# Dot_Matrix.net
KiCad netlist of a schematic drawn in Altium Designer
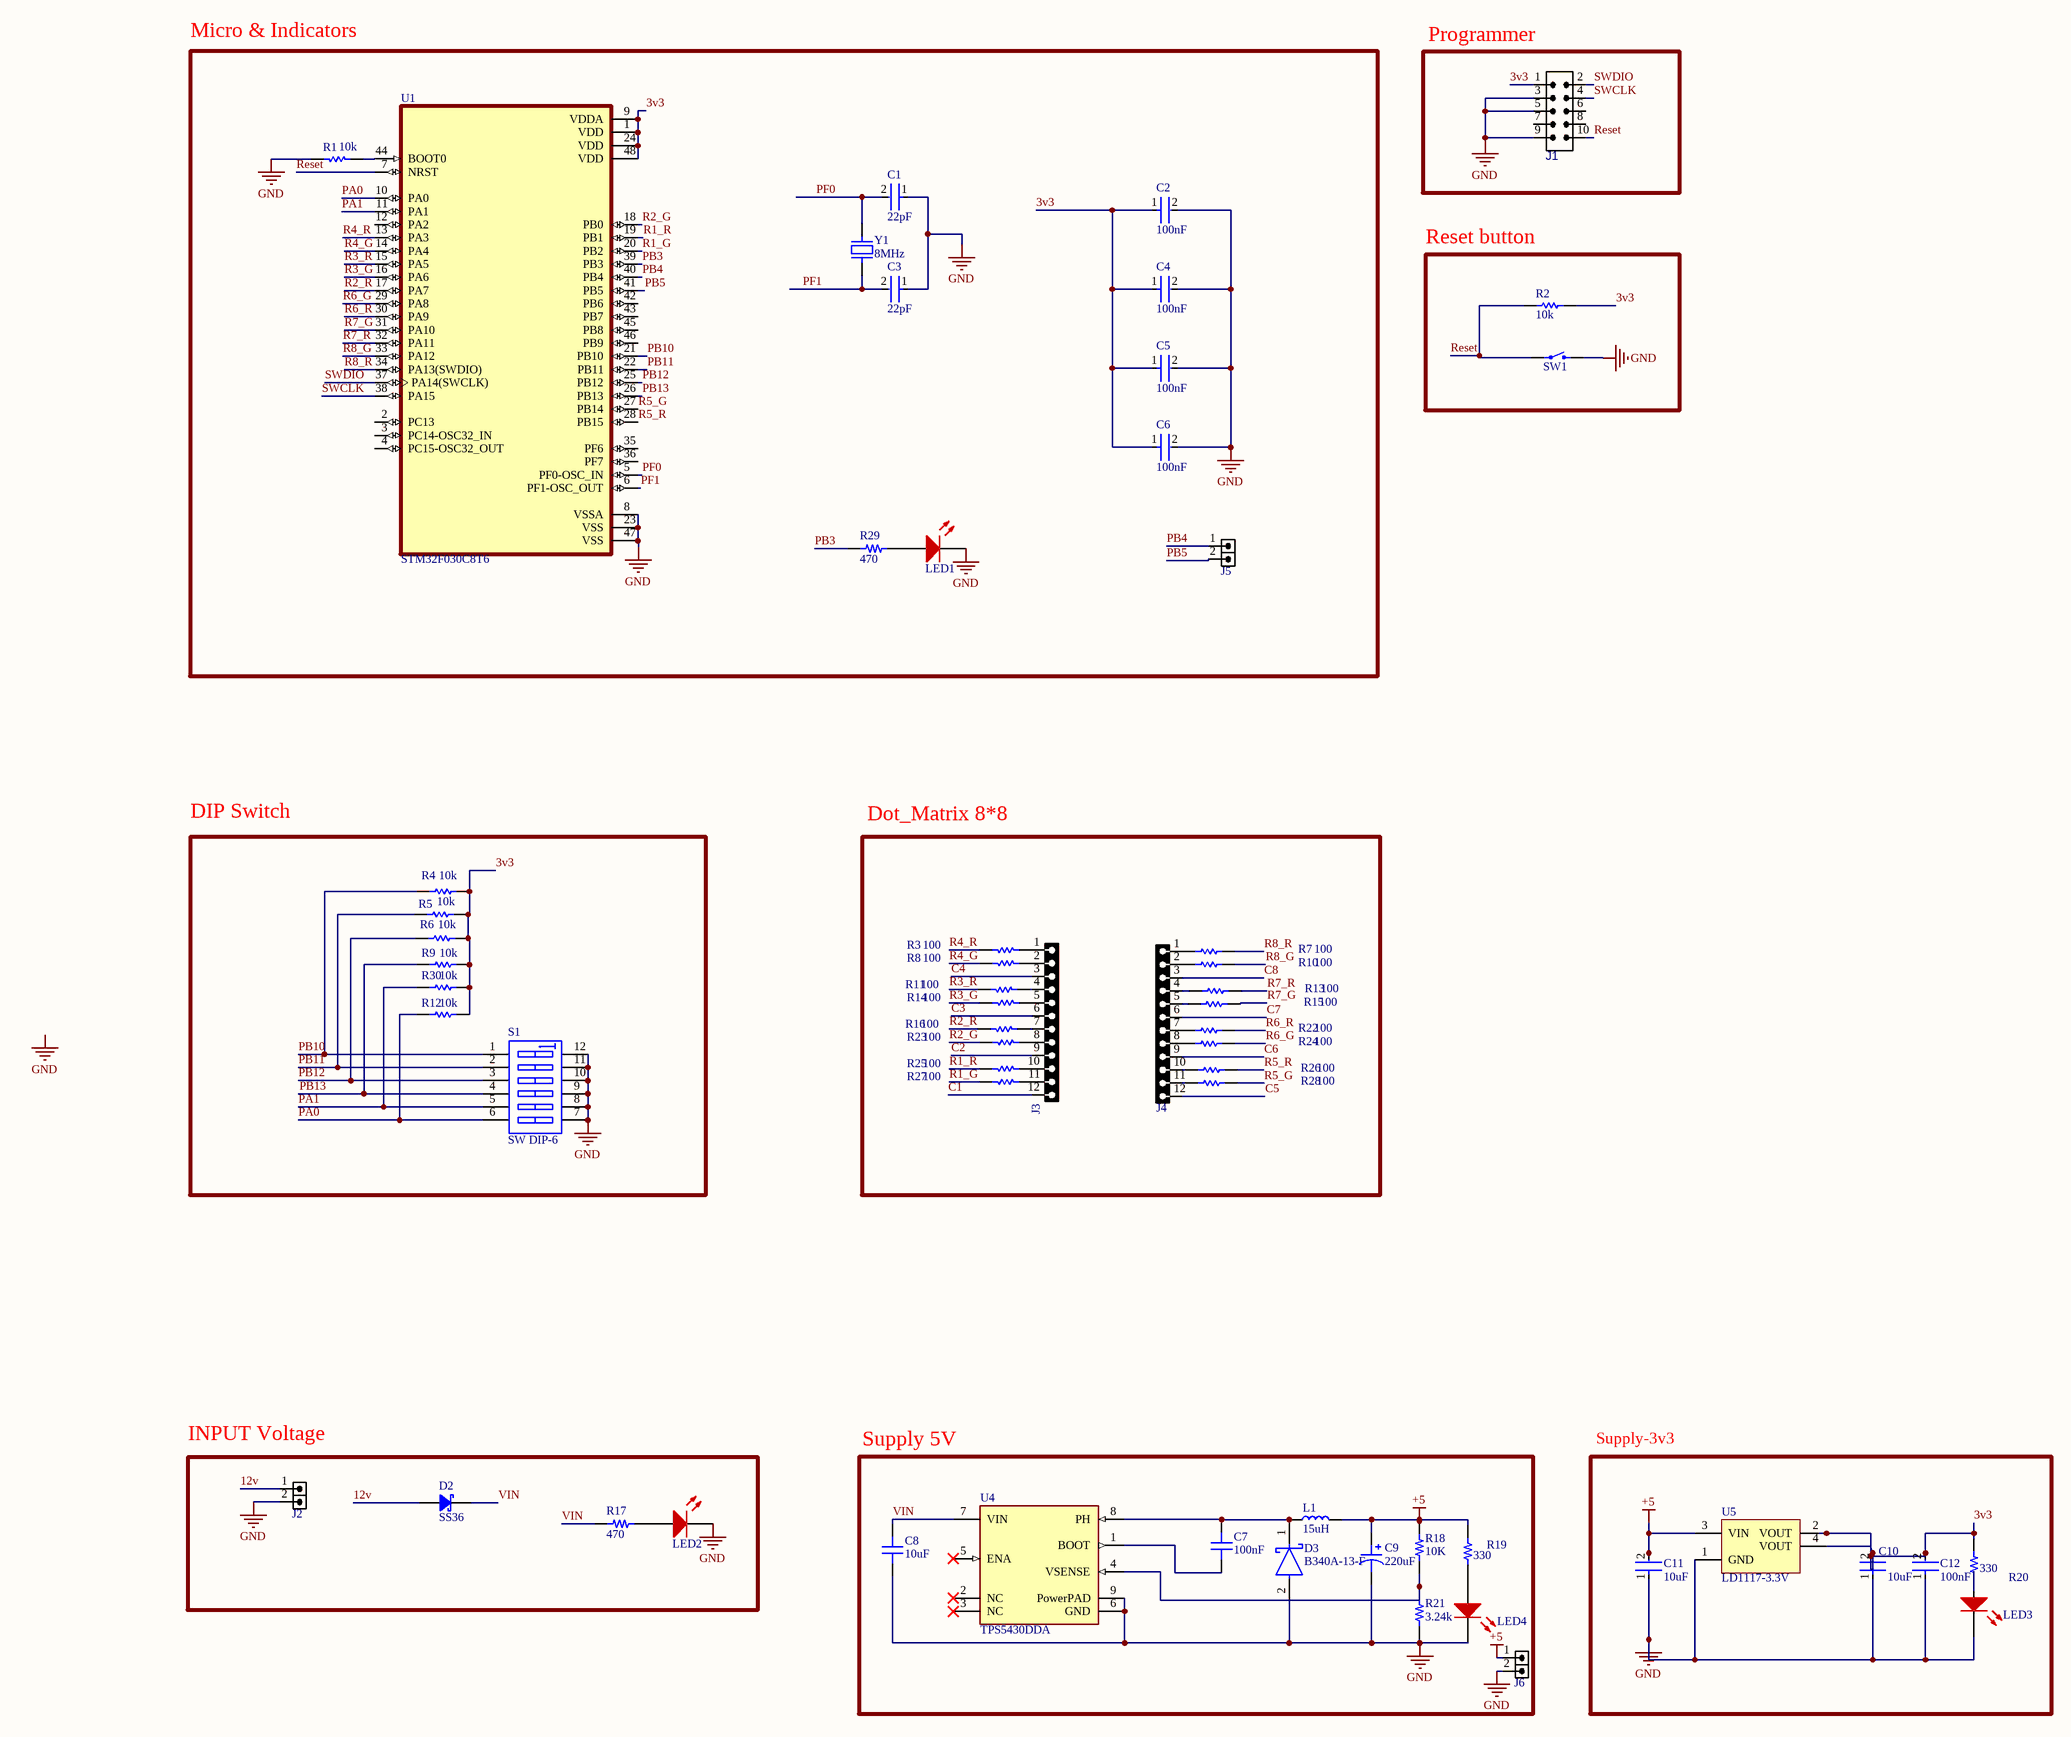
[diagram p0: Dot_Matrix.SchDoc]

(export (version "E")
  (design (tool "Eeschema 10.0.6"))
  (components
    (comp (ref "C1")
      (value "22pF")
      (footprint "FP-C0805C-DN-MFG")
      (description "CAP CER 0.22UF 50V X7R 0805")
      (fields
        (field (name "MANUFACTURER") "KEMET")
        (field (name "OCTOPART") "https://octopart.com/c0805c224k5ractu-kemet-144670")
      )
      (libsource (lib "Altium Content Vault") (part "b4654b650e69147ec39a6b967a45e02"))
    )
    (comp (ref "C2")
      (value "100nF")
      (footprint "FP-C0805C-DN-MFG")
      (description "CAP CER 0.22UF 50V X7R 0805")
      (fields
        (field (name "MANUFACTURER") "KEMET")
        (field (name "OCTOPART") "https://octopart.com/c0805c224k5ractu-kemet-144670")
      )
      (libsource (lib "Altium Content Vault") (part "b4654b650e69147ec39a6b967a45e02"))
    )
    (comp (ref "C3")
      (value "22pF")
      (footprint "FP-C0805C-DN-MFG")
      (description "CAP CER 0.22UF 50V X7R 0805")
      (fields
        (field (name "MANUFACTURER") "KEMET")
        (field (name "OCTOPART") "https://octopart.com/c0805c224k5ractu-kemet-144670")
      )
      (libsource (lib "Altium Content Vault") (part "b4654b650e69147ec39a6b967a45e02"))
    )
    (comp (ref "C4")
      (value "100nF")
      (footprint "FP-C0805C-DN-MFG")
      (description "CAP CER 0.22UF 50V X7R 0805")
      (fields
        (field (name "MANUFACTURER") "KEMET")
        (field (name "OCTOPART") "https://octopart.com/c0805c224k5ractu-kemet-144670")
      )
      (libsource (lib "Altium Content Vault") (part "b4654b650e69147ec39a6b967a45e02"))
    )
    (comp (ref "C5")
      (value "100nF")
      (footprint "FP-C0805C-DN-MFG")
      (description "CAP CER 0.22UF 50V X7R 0805")
      (fields
        (field (name "MANUFACTURER") "KEMET")
        (field (name "OCTOPART") "https://octopart.com/c0805c224k5ractu-kemet-144670")
      )
      (libsource (lib "Altium Content Vault") (part "b4654b650e69147ec39a6b967a45e02"))
    )
    (comp (ref "C6")
      (value "100nF")
      (footprint "FP-C0805C-DN-MFG")
      (description "CAP CER 0.22UF 50V X7R 0805")
      (fields
        (field (name "MANUFACTURER") "KEMET")
        (field (name "OCTOPART") "https://octopart.com/c0805c224k5ractu-kemet-144670")
      )
      (libsource (lib "Altium Content Vault") (part "b4654b650e69147ec39a6b967a45e02"))
    )
    (comp (ref "C7")
      (value "100nF")
      (footprint "CAP 0805_2012")
      (description "SMT Capacitor")
      (libsource (lib "Capacitor") (part "Cap 0805"))
    )
    (comp (ref "C8")
      (value "10uF")
      (footprint "CAP 0805_2012")
      (description "SMT Capacitor")
      (libsource (lib "Capacitor") (part "Cap 0805"))
    )
    (comp (ref "C9")
      (value "220uF")
      (footprint "CAP TANSMD 1206_3216 CASE A")
      (description "SMT Tantalum Capacitor")
      (libsource (lib "Capacitor") (part "Cap Tan Case A"))
    )
    (comp (ref "C10")
      (value "10uF")
      (footprint "FP-C0805C-DN-MFG")
      (description "CAP CER 0.22UF 50V X7R 0805")
      (fields
        (field (name "MANUFACTURER") "KEMET")
        (field (name "OCTOPART") "https://octopart.com/c0805c224k5ractu-kemet-144670")
      )
      (libsource (lib "Altium Content Vault") (part "b4654b650e69147ec39a6b967a45e02"))
    )
    (comp (ref "C11")
      (value "10uF")
      (footprint "FP-C0805C-DN-MFG")
      (description "CAP CER 0.22UF 50V X7R 0805")
      (fields
        (field (name "MANUFACTURER") "KEMET")
        (field (name "OCTOPART") "https://octopart.com/c0805c224k5ractu-kemet-144670")
      )
      (libsource (lib "Altium Content Vault") (part "b4654b650e69147ec39a6b967a45e02"))
    )
    (comp (ref "C12")
      (value "100nF")
      (footprint "FP-C0805C-DN-MFG")
      (description "CAP CER 0.22UF 50V X7R 0805")
      (fields
        (field (name "MANUFACTURER") "KEMET")
        (field (name "OCTOPART") "https://octopart.com/c0805c224k5ractu-kemet-144670")
      )
      (libsource (lib "Altium Content Vault") (part "b4654b650e69147ec39a6b967a45e02"))
    )
    (comp (ref "D2")
      (value "SS36")
      (footprint "DO-214AA SMB")
      (description "Diode Schottky 60V 3A Surface Mount DO-214AB (SMC)")
      (fields (field (name "PARTNUMBER") "SS36-E3/57T"))
      (libsource (lib "Diode") (part "SS36 (SMD SMC)"))
    )
    (comp (ref "D3")
      (value "B340A-13-F")
      (footprint "FP-SMA-MFG")
      (description "DIODE SCHOTTKY 40V 3A SMA")
      (fields (field (name "VOLTAGE") "40V"))
      (libsource (lib "Altium Content Vault") (part "1d6ec82d83fb6aee721767c19dac4b9"))
    )
    (comp (ref "J1")
      (value "IDC_2X5")
      (footprint "IDC_2X5")
      (description "CONN, IDC, Male, pitch: 2.54mm, 10POS")
      (libsource (lib "Conn Header") (part "IDC_2X5"))
    )
    (comp (ref "J2")
      (value "HDRM2")
      (footprint "HDR_1X2")
      (description "CONN, HEADER, Male, pitch: 2.54mm, 2POS")
      (libsource (lib "Conn Header") (part "HDR_1X2"))
    )
    (comp (ref "J3")
      (value "HDRF12")
      (footprint "HDR_F_1X12")
      (description "CONN, HEADER, Female, pitch: 2.54mm, 12POS")
      (libsource (lib "Conn Header") (part "HDR_F_1X12"))
    )
    (comp (ref "J4")
      (value "HDRF12")
      (footprint "HDR_F_1X12")
      (description "CONN, HEADER, Female, pitch: 2.54mm, 12POS")
      (libsource (lib "") (part "HDR_F_1X12_1"))
    )
    (comp (ref "J5")
      (value "HDRM2")
      (footprint "HDR_1X2")
      (description "CONN, HEADER, Male, pitch: 2.54mm, 2POS")
      (libsource (lib "Conn Header") (part "HDR_1X2"))
    )
    (comp (ref "J6")
      (value "HDRM2")
      (footprint "HDR_1X2")
      (description "CONN, HEADER, Male, pitch: 2.54mm, 2POS")
      (libsource (lib "Conn Header") (part "HDR_1X2"))
    )
    (comp (ref "L1")
      (value "15uH")
      (footprint "IND 0805_2012")
      (description "SMT Inductor")
      (libsource (lib "Inductor") (part "Ind 0805"))
    )
    (comp (ref "LED1")
      (value "LED SMD 0805 RED")
      (footprint "LED_0805_RED")
      (libsource (lib "Led") (part "LED SMD 0805 RED"))
    )
    (comp (ref "LED2")
      (value "LED SMD 0805 RED")
      (footprint "LED_0805_RED")
      (libsource (lib "Led") (part "LED SMD 0805 RED"))
    )
    (comp (ref "LED3")
      (value "LED SMD 0805 RED")
      (footprint "LED_0805_RED")
      (libsource (lib "Led") (part "LED SMD 0805 RED"))
    )
    (comp (ref "LED4")
      (value "LED SMD 0805 RED")
      (footprint "LED_0805_RED")
      (libsource (lib "Led") (part "LED SMD 0805 RED"))
    )
    (comp (ref "R1")
      (value "10k")
      (footprint "RESC2013X60X35ML10T20")
      (fields (field (name "TOLERANCE") "5%") (field (name "MANUFACTURER") "Yageo"))
      (libsource (lib "Altium Content Vault") (part "RES-2"))
    )
    (comp (ref "R2")
      (value "10k")
      (footprint "RESC2013X60X35ML10T20")
      (fields (field (name "TOLERANCE") "5%") (field (name "MANUFACTURER") "Yageo"))
      (libsource (lib "Altium Content Vault") (part "RES-2"))
    )
    (comp (ref "R3")
      (value "100")
      (footprint "RESC2013X60X35ML10T20")
      (fields (field (name "TOLERANCE") "5%") (field (name "MANUFACTURER") "Yageo"))
      (libsource (lib "Altium Content Vault") (part "RES-2"))
    )
    (comp (ref "R4")
      (value "10k")
      (footprint "RESC2013X60X35ML10T20")
      (fields (field (name "TOLERANCE") "5%") (field (name "MANUFACTURER") "Yageo"))
      (libsource (lib "Altium Content Vault") (part "RES-2"))
    )
    (comp (ref "R5")
      (value "10k")
      (footprint "RESC2013X60X35ML10T20")
      (fields (field (name "TOLERANCE") "5%") (field (name "MANUFACTURER") "Yageo"))
      (libsource (lib "Altium Content Vault") (part "RES-2"))
    )
    (comp (ref "R6")
      (value "10k")
      (footprint "RESC2013X60X35ML10T20")
      (fields (field (name "TOLERANCE") "5%") (field (name "MANUFACTURER") "Yageo"))
      (libsource (lib "Altium Content Vault") (part "RES-2"))
    )
    (comp (ref "R7")
      (value "100")
      (footprint "RESC2013X60X35ML10T20")
      (fields (field (name "TOLERANCE") "5%") (field (name "MANUFACTURER") "Yageo"))
      (libsource (lib "Altium Content Vault") (part "RES-2"))
    )
    (comp (ref "R8")
      (value "100")
      (footprint "RESC2013X60X35ML10T20")
      (fields (field (name "TOLERANCE") "5%") (field (name "MANUFACTURER") "Yageo"))
      (libsource (lib "Altium Content Vault") (part "RES-2"))
    )
    (comp (ref "R9")
      (value "10k")
      (footprint "RESC2013X60X35ML10T20")
      (fields (field (name "TOLERANCE") "5%") (field (name "MANUFACTURER") "Yageo"))
      (libsource (lib "Altium Content Vault") (part "RES-2"))
    )
    (comp (ref "R10")
      (value "100")
      (footprint "RESC2013X60X35ML10T20")
      (fields (field (name "TOLERANCE") "5%") (field (name "MANUFACTURER") "Yageo"))
      (libsource (lib "Altium Content Vault") (part "RES-2"))
    )
    (comp (ref "R11")
      (value "100")
      (footprint "RESC2013X60X35ML10T20")
      (fields (field (name "TOLERANCE") "5%") (field (name "MANUFACTURER") "Yageo"))
      (libsource (lib "Altium Content Vault") (part "RES-2"))
    )
    (comp (ref "R12")
      (value "10k")
      (footprint "RESC2013X60X35ML10T20")
      (fields (field (name "TOLERANCE") "5%") (field (name "MANUFACTURER") "Yageo"))
      (libsource (lib "Altium Content Vault") (part "RES-2"))
    )
    (comp (ref "R13")
      (value "100")
      (footprint "RESC2013X60X35ML10T20")
      (fields (field (name "TOLERANCE") "5%") (field (name "MANUFACTURER") "Yageo"))
      (libsource (lib "Altium Content Vault") (part "RES-2"))
    )
    (comp (ref "R14")
      (value "100")
      (footprint "RESC2013X60X35ML10T20")
      (fields (field (name "TOLERANCE") "5%") (field (name "MANUFACTURER") "Yageo"))
      (libsource (lib "Altium Content Vault") (part "RES-2"))
    )
    (comp (ref "R15")
      (value "100")
      (footprint "RESC2013X60X35ML10T20")
      (fields (field (name "TOLERANCE") "5%") (field (name "MANUFACTURER") "Yageo"))
      (libsource (lib "Altium Content Vault") (part "RES-2"))
    )
    (comp (ref "R16")
      (value "100")
      (footprint "RESC2013X60X35ML10T20")
      (fields (field (name "TOLERANCE") "5%") (field (name "MANUFACTURER") "Yageo"))
      (libsource (lib "Altium Content Vault") (part "RES-2"))
    )
    (comp (ref "R17")
      (value "470")
      (footprint "RES 0805_2012")
      (description "SMT Resistor")
      (libsource (lib "Resistor") (part "Res 0805"))
    )
    (comp (ref "R18")
      (value "10K")
      (footprint "RES 0805_2012")
      (description "SMT Resistor")
      (libsource (lib "Resistor") (part "Res 0805"))
    )
    (comp (ref "R19")
      (value "330")
      (footprint "RES 0805_2012")
      (description "SMT Resistor")
      (libsource (lib "Resistor") (part "Res 0805"))
    )
    (comp (ref "R20")
      (value "330")
      (footprint "RES 0805_2012")
      (description "SMT Resistor")
      (libsource (lib "Resistor") (part "Res 0805"))
    )
    (comp (ref "R21")
      (value "3.24k")
      (footprint "RES 0805_2012")
      (description "SMT Resistor")
      (libsource (lib "Resistor") (part "Res 0805"))
    )
    (comp (ref "R22")
      (value "100")
      (footprint "RESC2013X60X35ML10T20")
      (fields (field (name "TOLERANCE") "5%") (field (name "MANUFACTURER") "Yageo"))
      (libsource (lib "Altium Content Vault") (part "RES-2"))
    )
    (comp (ref "R23")
      (value "100")
      (footprint "RESC2013X60X35ML10T20")
      (fields (field (name "TOLERANCE") "5%") (field (name "MANUFACTURER") "Yageo"))
      (libsource (lib "Altium Content Vault") (part "RES-2"))
    )
    (comp (ref "R24")
      (value "100")
      (footprint "RESC2013X60X35ML10T20")
      (fields (field (name "TOLERANCE") "5%") (field (name "MANUFACTURER") "Yageo"))
      (libsource (lib "Altium Content Vault") (part "RES-2"))
    )
    (comp (ref "R25")
      (value "100")
      (footprint "RESC2013X60X35ML10T20")
      (fields (field (name "TOLERANCE") "5%") (field (name "MANUFACTURER") "Yageo"))
      (libsource (lib "Altium Content Vault") (part "RES-2"))
    )
    (comp (ref "R26")
      (value "100")
      (footprint "RESC2013X60X35ML10T20")
      (fields (field (name "TOLERANCE") "5%") (field (name "MANUFACTURER") "Yageo"))
      (libsource (lib "Altium Content Vault") (part "RES-2"))
    )
    (comp (ref "R27")
      (value "100")
      (footprint "RESC2013X60X35ML10T20")
      (fields (field (name "TOLERANCE") "5%") (field (name "MANUFACTURER") "Yageo"))
      (libsource (lib "Altium Content Vault") (part "RES-2"))
    )
    (comp (ref "R28")
      (value "100")
      (footprint "RESC2013X60X35ML10T20")
      (fields (field (name "TOLERANCE") "5%") (field (name "MANUFACTURER") "Yageo"))
      (libsource (lib "Altium Content Vault") (part "RES-2"))
    )
    (comp (ref "R29")
      (value "470")
      (footprint "RES 0805_2012")
      (description "SMT Resistor")
      (libsource (lib "Resistor") (part "Res 0805"))
    )
    (comp (ref "R30")
      (value "10k")
      (footprint "RESC2013X60X35ML10T20")
      (fields (field (name "TOLERANCE") "5%") (field (name "MANUFACTURER") "Yageo"))
      (libsource (lib "Altium Content Vault") (part "RES-2"))
    )
    (comp (ref "S1")
      (value "SW DIP-6")
      (footprint "DIP-12/SW")
      (description "DIP Switch, 6 Position, SPST")
      (fields (field (name "PUBLISHER") "Altium Limited"))
      (libsource (lib "Miscellaneous Devices") (part "SW DIP-6"))
    )
    (comp (ref "SW1")
      (value "Tactile 2PIN 6X3.5mm H4.57mm (SMD)")
      (footprint "SWPBS_SPST_6X3X5")
      (description "Tactile Switch SPST-NO Top Actuated Surface Mount")
      (fields (field (name "PARTNUMBER") "FSMSMTR-ND"))
      (libsource (lib "Switch") (part "Tactile 2PIN 6X3.5mm H4.57mm (SMD)"))
    )
    (comp (ref "U1")
      (value "STM32F030C8T6")
      (footprint "QFP50P900X900X160-48N")
      (description "STM32F Series 32-bit 64 kB Flash 8 kB RAM ARM Based Microcontroller - LQFP-48")
      (libsource (lib "STM32F030C8T6") (part "STM32F030C8T6"))
    )
    (comp (ref "U4")
      (value "TPS5430DDA")
      (footprint "FP-DDA0008J-MFG")
      (description "IC REG BUCK ADJUSTABLE 3A 8SOPWR")
      (fields
        (field (name "MANUFACTURER") "Texas Instruments")
        (field (name "OCTOPART") "https://octopart.com/tps5430dda-texas+instruments-589977")
      )
      (libsource (lib "Altium Content Vault") (part "98da629940cea6febc5630bb55159f3"))
    )
    (comp (ref "U5")
      (value "LD1117-3.3V")
      (footprint "SOT-223-4 6.5X7MM P2.3MM")
      (description "Linear Voltage Regulator IC  1 Output  800mA SOT-223")
      (fields (field (name "PARTNUMBER") "LD1117S33CTR"))
      (libsource (lib "Chip") (part "LD1117-3.3V (SMD SOT-223)"))
    )
    (comp (ref "Y1")
      (value "8MHz")
      (footprint "HC-49S SMD")
      (description "SMT Crystal")
      (fields (field (name "PARTNUMBER") "ABLS-8.000MHZ-K4T"))
      (libsource (lib "Xtal") (part "Crystal HC-49S SMD 8MHz"))
    )
  )
  (nets
    (net (code "1") (name "+5") (class "Default")
      (node (ref "C11") (pin "2") (pinfunction "2_2") (pintype "passive"))
      (node (ref "C9") (pin "1") (pinfunction "1_1") (pintype "passive"))
      (node (ref "J6") (pin "1") (pinfunction "1_1") (pintype "passive"))
      (node (ref "L1") (pin "2") (pinfunction "2_2") (pintype "passive"))
      (node (ref "R18") (pin "2") (pinfunction "2_2") (pintype "passive"))
      (node (ref "R19") (pin "1") (pinfunction "1_1") (pintype "passive"))
      (node (ref "U5") (pin "3") (pinfunction "VIN_3") (pintype "passive"))
    )
    (net (code "2") (name "/3v3") (class "Default")
      (node (ref "C10") (pin "2") (pinfunction "2_2") (pintype "passive"))
      (node (ref "C12") (pin "2") (pinfunction "2_2") (pintype "passive"))
      (node (ref "C2") (pin "1") (pinfunction "1_1") (pintype "passive"))
      (node (ref "C4") (pin "1") (pinfunction "1_1") (pintype "passive"))
      (node (ref "C5") (pin "1") (pinfunction "1_1") (pintype "passive"))
      (node (ref "C6") (pin "1") (pinfunction "1_1") (pintype "passive"))
      (node (ref "J1") (pin "1") (pinfunction "1_1") (pintype "passive"))
      (node (ref "R12") (pin "1") (pinfunction "1_1") (pintype "passive"))
      (node (ref "R2") (pin "1") (pinfunction "1_1") (pintype "passive"))
      (node (ref "R20") (pin "1") (pinfunction "1_1") (pintype "passive"))
      (node (ref "R30") (pin "1") (pinfunction "1_1") (pintype "passive"))
      (node (ref "R4") (pin "1") (pinfunction "1_1") (pintype "passive"))
      (node (ref "R5") (pin "1") (pinfunction "1_1") (pintype "passive"))
      (node (ref "R6") (pin "1") (pinfunction "1_1") (pintype "passive"))
      (node (ref "R9") (pin "1") (pinfunction "1_1") (pintype "passive"))
      (node (ref "U1") (pin "1") (pinfunction "VDD_1") (pintype "power_in"))
      (node (ref "U1") (pin "24") (pinfunction "VDD_24") (pintype "power_in"))
      (node (ref "U1") (pin "48") (pinfunction "VDD_48") (pintype "power_in"))
      (node (ref "U1") (pin "9") (pinfunction "VDDA_9") (pintype "power_in"))
      (node (ref "U5") (pin "2") (pinfunction "VOUT_2") (pintype "passive"))
      (node (ref "U5") (pin "4") (pinfunction "VOUT_4") (pintype "passive"))
    )
    (net (code "3") (name "/12v") (class "Default")
      (node (ref "D2") (pin "1") (pinfunction "1_1") (pintype "passive"))
      (node (ref "J2") (pin "1") (pinfunction "1_1") (pintype "passive"))
    )
    (net (code "4") (name "/C1") (class "Default")
      (node (ref "J3") (pin "12") (pinfunction "12_12") (pintype "passive"))
    )
    (net (code "5") (name "/C2") (class "Default")
      (node (ref "J3") (pin "9") (pinfunction "9_9") (pintype "passive"))
    )
    (net (code "6") (name "/C3") (class "Default")
      (node (ref "J3") (pin "6") (pinfunction "6_6") (pintype "passive"))
    )
    (net (code "7") (name "/C4") (class "Default")
      (node (ref "J3") (pin "3") (pinfunction "3_3") (pintype "passive"))
    )
    (net (code "8") (name "/C5") (class "Default")
      (node (ref "J4") (pin "12") (pinfunction "12_12") (pintype "passive"))
    )
    (net (code "9") (name "/C6") (class "Default")
      (node (ref "J4") (pin "9") (pinfunction "9_9") (pintype "passive"))
    )
    (net (code "10") (name "/C7") (class "Default")
      (node (ref "J4") (pin "6") (pinfunction "6_6") (pintype "passive"))
    )
    (net (code "11") (name "/C8") (class "Default")
      (node (ref "J4") (pin "3") (pinfunction "3_3") (pintype "passive"))
    )
    (net (code "12") (name "/PA0") (class "Default")
      (node (ref "R12") (pin "2") (pinfunction "2_2") (pintype "passive"))
      (node (ref "S1") (pin "6") (pinfunction "A6_6") (pintype "passive"))
      (node (ref "U1") (pin "10") (pinfunction "PA0_10") (pintype "bidirectional"))
    )
    (net (code "13") (name "/PA1") (class "Default")
      (node (ref "R30") (pin "2") (pinfunction "2_2") (pintype "passive"))
      (node (ref "S1") (pin "5") (pinfunction "A5_5") (pintype "passive"))
      (node (ref "U1") (pin "11") (pinfunction "PA1_11") (pintype "bidirectional"))
    )
    (net (code "14") (name "/PB3") (class "Default")
      (node (ref "R29") (pin "1") (pinfunction "1_1") (pintype "passive"))
      (node (ref "U1") (pin "39") (pinfunction "PB3_39") (pintype "bidirectional"))
    )
    (net (code "15") (name "/PB4") (class "Default")
      (node (ref "J5") (pin "1") (pinfunction "1_1") (pintype "passive"))
      (node (ref "U1") (pin "40") (pinfunction "PB4_40") (pintype "bidirectional"))
    )
    (net (code "16") (name "/PB5") (class "Default")
      (node (ref "J5") (pin "2") (pinfunction "2_2") (pintype "passive"))
      (node (ref "U1") (pin "41") (pinfunction "PB5_41") (pintype "bidirectional"))
    )
    (net (code "17") (name "/PB10") (class "Default")
      (node (ref "R4") (pin "2") (pinfunction "2_2") (pintype "passive"))
      (node (ref "S1") (pin "1") (pinfunction "A1_1") (pintype "passive"))
      (node (ref "U1") (pin "21") (pinfunction "PB10_21") (pintype "bidirectional"))
    )
    (net (code "18") (name "/PB11") (class "Default")
      (node (ref "R5") (pin "2") (pinfunction "2_2") (pintype "passive"))
      (node (ref "S1") (pin "2") (pinfunction "A2_2") (pintype "passive"))
      (node (ref "U1") (pin "22") (pinfunction "PB11_22") (pintype "bidirectional"))
    )
    (net (code "19") (name "/PB12") (class "Default")
      (node (ref "R6") (pin "2") (pinfunction "2_2") (pintype "passive"))
      (node (ref "S1") (pin "3") (pinfunction "A3_3") (pintype "passive"))
      (node (ref "U1") (pin "25") (pinfunction "PB12_25") (pintype "bidirectional"))
    )
    (net (code "20") (name "/PB13") (class "Default")
      (node (ref "R9") (pin "2") (pinfunction "2_2") (pintype "passive"))
      (node (ref "S1") (pin "4") (pinfunction "A4_4") (pintype "passive"))
      (node (ref "U1") (pin "26") (pinfunction "PB13_26") (pintype "bidirectional"))
    )
    (net (code "21") (name "/PF0") (class "Default")
      (node (ref "C1") (pin "2") (pinfunction "2_2") (pintype "passive"))
      (node (ref "U1") (pin "5") (pinfunction "PF0-OSC_IN_5") (pintype "bidirectional"))
      (node (ref "Y1") (pin "2") (pinfunction "2_2") (pintype "passive"))
    )
    (net (code "22") (name "/PF1") (class "Default")
      (node (ref "C3") (pin "2") (pinfunction "2_2") (pintype "passive"))
      (node (ref "U1") (pin "6") (pinfunction "PF1-OSC_OUT_6") (pintype "bidirectional"))
      (node (ref "Y1") (pin "1") (pinfunction "1_1") (pintype "passive"))
    )
    (net (code "23") (name "/R1_G") (class "Default")
      (node (ref "R27") (pin "1") (pinfunction "1_1") (pintype "passive"))
      (node (ref "U1") (pin "20") (pinfunction "PB2_20") (pintype "bidirectional"))
    )
    (net (code "24") (name "/R1_R") (class "Default")
      (node (ref "R25") (pin "1") (pinfunction "1_1") (pintype "passive"))
      (node (ref "U1") (pin "19") (pinfunction "PB1_19") (pintype "bidirectional"))
    )
    (net (code "25") (name "/R2_G") (class "Default")
      (node (ref "R23") (pin "1") (pinfunction "1_1") (pintype "passive"))
      (node (ref "U1") (pin "18") (pinfunction "PB0_18") (pintype "bidirectional"))
    )
    (net (code "26") (name "/R2_R") (class "Default")
      (node (ref "R16") (pin "1") (pinfunction "1_1") (pintype "passive"))
      (node (ref "U1") (pin "17") (pinfunction "PA7_17") (pintype "bidirectional"))
    )
    (net (code "27") (name "/R3_G") (class "Default")
      (node (ref "R14") (pin "1") (pinfunction "1_1") (pintype "passive"))
      (node (ref "U1") (pin "16") (pinfunction "PA6_16") (pintype "bidirectional"))
    )
    (net (code "28") (name "/R3_R") (class "Default")
      (node (ref "R11") (pin "1") (pinfunction "1_1") (pintype "passive"))
      (node (ref "U1") (pin "15") (pinfunction "PA5_15") (pintype "bidirectional"))
    )
    (net (code "29") (name "/R4_G") (class "Default")
      (node (ref "R8") (pin "1") (pinfunction "1_1") (pintype "passive"))
      (node (ref "U1") (pin "14") (pinfunction "PA4_14") (pintype "bidirectional"))
    )
    (net (code "30") (name "/R4_R") (class "Default")
      (node (ref "R3") (pin "1") (pinfunction "1_1") (pintype "passive"))
      (node (ref "U1") (pin "13") (pinfunction "PA3_13") (pintype "bidirectional"))
    )
    (net (code "31") (name "/R5_G") (class "Default")
      (node (ref "R28") (pin "1") (pinfunction "1_1") (pintype "passive"))
      (node (ref "U1") (pin "27") (pinfunction "PB14_27") (pintype "bidirectional"))
    )
    (net (code "32") (name "/R5_R") (class "Default")
      (node (ref "R26") (pin "1") (pinfunction "1_1") (pintype "passive"))
      (node (ref "U1") (pin "28") (pinfunction "PB15_28") (pintype "bidirectional"))
    )
    (net (code "33") (name "/R6_G") (class "Default")
      (node (ref "R24") (pin "1") (pinfunction "1_1") (pintype "passive"))
      (node (ref "U1") (pin "29") (pinfunction "PA8_29") (pintype "bidirectional"))
    )
    (net (code "34") (name "/R6_R") (class "Default")
      (node (ref "R22") (pin "1") (pinfunction "1_1") (pintype "passive"))
      (node (ref "U1") (pin "30") (pinfunction "PA9_30") (pintype "bidirectional"))
    )
    (net (code "35") (name "/R7_G") (class "Default")
      (node (ref "R15") (pin "1") (pinfunction "1_1") (pintype "passive"))
      (node (ref "U1") (pin "31") (pinfunction "PA10_31") (pintype "bidirectional"))
    )
    (net (code "36") (name "/R7_R") (class "Default")
      (node (ref "R13") (pin "1") (pinfunction "1_1") (pintype "passive"))
      (node (ref "U1") (pin "32") (pinfunction "PA11_32") (pintype "bidirectional"))
    )
    (net (code "37") (name "/R8_G") (class "Default")
      (node (ref "R10") (pin "1") (pinfunction "1_1") (pintype "passive"))
      (node (ref "U1") (pin "33") (pinfunction "PA12_33") (pintype "bidirectional"))
    )
    (net (code "38") (name "/R8_R") (class "Default")
      (node (ref "R7") (pin "1") (pinfunction "1_1") (pintype "passive"))
      (node (ref "U1") (pin "34") (pinfunction "PA13(SWDIO)_34") (pintype "bidirectional"))
    )
    (net (code "39") (name "/Reset") (class "Default")
      (node (ref "J1") (pin "10") (pinfunction "10_10") (pintype "passive"))
      (node (ref "R2") (pin "2") (pinfunction "2_2") (pintype "passive"))
      (node (ref "SW1") (pin "1") (pinfunction "1_1") (pintype "passive"))
      (node (ref "U1") (pin "7") (pinfunction "NRST_7") (pintype "bidirectional"))
    )
    (net (code "40") (name "/SWCLK") (class "Default")
      (node (ref "J1") (pin "4") (pinfunction "4_4") (pintype "passive"))
      (node (ref "U1") (pin "38") (pinfunction "PA15_38") (pintype "bidirectional"))
    )
    (net (code "41") (name "/SWDIO") (class "Default")
      (node (ref "J1") (pin "2") (pinfunction "2_2") (pintype "passive"))
      (node (ref "U1") (pin "37") (pinfunction "PA14(SWCLK)_37") (pintype "bidirectional"))
    )
    (net (code "42") (name "/VIN") (class "Default")
      (node (ref "C8") (pin "2") (pinfunction "2_2") (pintype "passive"))
      (node (ref "D2") (pin "2") (pinfunction "2_2") (pintype "passive"))
      (node (ref "R17") (pin "1") (pinfunction "1_1") (pintype "passive"))
      (node (ref "U4") (pin "7") (pinfunction "VIN_7") (pintype "power_in"))
    )
    (net (code "43") (name "GND") (class "Default")
      (node (ref "C1") (pin "1") (pinfunction "1_1") (pintype "passive"))
      (node (ref "C10") (pin "1") (pinfunction "1_1") (pintype "passive"))
      (node (ref "C11") (pin "1") (pinfunction "1_1") (pintype "passive"))
      (node (ref "C12") (pin "1") (pinfunction "1_1") (pintype "passive"))
      (node (ref "C2") (pin "2") (pinfunction "2_2") (pintype "passive"))
      (node (ref "C3") (pin "1") (pinfunction "1_1") (pintype "passive"))
      (node (ref "C4") (pin "2") (pinfunction "2_2") (pintype "passive"))
      (node (ref "C5") (pin "2") (pinfunction "2_2") (pintype "passive"))
      (node (ref "C6") (pin "2") (pinfunction "2_2") (pintype "passive"))
      (node (ref "C8") (pin "1") (pinfunction "1_1") (pintype "passive"))
      (node (ref "C9") (pin "2") (pinfunction "2_2") (pintype "passive"))
      (node (ref "D3") (pin "2") (pinfunction "A_2") (pintype "passive"))
      (node (ref "J1") (pin "3") (pinfunction "3_3") (pintype "passive"))
      (node (ref "J1") (pin "5") (pinfunction "5_5") (pintype "passive"))
      (node (ref "J1") (pin "9") (pinfunction "9_9") (pintype "passive"))
      (node (ref "J2") (pin "2") (pinfunction "2_2") (pintype "passive"))
      (node (ref "J6") (pin "2") (pinfunction "2_2") (pintype "passive"))
      (node (ref "LED1") (pin "2") (pinfunction "K_2") (pintype "passive"))
      (node (ref "LED2") (pin "2") (pinfunction "K_2") (pintype "passive"))
      (node (ref "LED3") (pin "2") (pinfunction "K_2") (pintype "passive"))
      (node (ref "LED4") (pin "2") (pinfunction "K_2") (pintype "passive"))
      (node (ref "R1") (pin "1") (pinfunction "1_1") (pintype "passive"))
      (node (ref "R21") (pin "1") (pinfunction "1_1") (pintype "passive"))
      (node (ref "S1") (pin "10") (pinfunction "B3_10") (pintype "passive"))
      (node (ref "S1") (pin "11") (pinfunction "B2_11") (pintype "passive"))
      (node (ref "S1") (pin "12") (pinfunction "B1_12") (pintype "passive"))
      (node (ref "S1") (pin "7") (pinfunction "B6_7") (pintype "passive"))
      (node (ref "S1") (pin "8") (pinfunction "B5_8") (pintype "passive"))
      (node (ref "S1") (pin "9") (pinfunction "B4_9") (pintype "passive"))
      (node (ref "SW1") (pin "2") (pinfunction "2_2") (pintype "passive"))
      (node (ref "U1") (pin "23") (pinfunction "VSS_23") (pintype "power_in"))
      (node (ref "U1") (pin "47") (pinfunction "VSS_47") (pintype "power_in"))
      (node (ref "U1") (pin "8") (pinfunction "VSSA_8") (pintype "power_in"))
      (node (ref "U4") (pin "6") (pinfunction "GND_6") (pintype "power_in"))
      (node (ref "U4") (pin "9") (pinfunction "PowerPAD_9") (pintype "power_in"))
      (node (ref "U5") (pin "1") (pinfunction "GND_1") (pintype "passive"))
    )
    (net (code "44") (name "Net-(D3-C)") (class "Default")
      (node (ref "C7") (pin "2") (pinfunction "2_2") (pintype "passive"))
      (node (ref "D3") (pin "1") (pinfunction "C_1") (pintype "passive"))
      (node (ref "L1") (pin "1") (pinfunction "1_1") (pintype "passive"))
      (node (ref "U4") (pin "8") (pinfunction "PH_8") (pintype "input"))
    )
    (net (code "45") (name "Net-(J3-Pad1)") (class "Default")
      (node (ref "J3") (pin "1") (pinfunction "1_1") (pintype "passive"))
      (node (ref "R3") (pin "2") (pinfunction "2_2") (pintype "passive"))
    )
    (net (code "46") (name "Net-(J3-Pad2)") (class "Default")
      (node (ref "J3") (pin "2") (pinfunction "2_2") (pintype "passive"))
      (node (ref "R8") (pin "2") (pinfunction "2_2") (pintype "passive"))
    )
    (net (code "47") (name "Net-(J3-Pad4)") (class "Default")
      (node (ref "J3") (pin "4") (pinfunction "4_4") (pintype "passive"))
      (node (ref "R11") (pin "2") (pinfunction "2_2") (pintype "passive"))
    )
    (net (code "48") (name "Net-(J3-Pad5)") (class "Default")
      (node (ref "J3") (pin "5") (pinfunction "5_5") (pintype "passive"))
      (node (ref "R14") (pin "2") (pinfunction "2_2") (pintype "passive"))
    )
    (net (code "49") (name "Net-(J3-Pad7)") (class "Default")
      (node (ref "J3") (pin "7") (pinfunction "7_7") (pintype "passive"))
      (node (ref "R16") (pin "2") (pinfunction "2_2") (pintype "passive"))
    )
    (net (code "50") (name "Net-(J3-Pad8)") (class "Default")
      (node (ref "J3") (pin "8") (pinfunction "8_8") (pintype "passive"))
      (node (ref "R23") (pin "2") (pinfunction "2_2") (pintype "passive"))
    )
    (net (code "51") (name "Net-(J3-Pad10)") (class "Default")
      (node (ref "J3") (pin "10") (pinfunction "10_10") (pintype "passive"))
      (node (ref "R25") (pin "2") (pinfunction "2_2") (pintype "passive"))
    )
    (net (code "52") (name "Net-(J3-Pad11)") (class "Default")
      (node (ref "J3") (pin "11") (pinfunction "11_11") (pintype "passive"))
      (node (ref "R27") (pin "2") (pinfunction "2_2") (pintype "passive"))
    )
    (net (code "53") (name "Net-(J4-Pad1)") (class "Default")
      (node (ref "J4") (pin "1") (pinfunction "1_1") (pintype "passive"))
      (node (ref "R7") (pin "2") (pinfunction "2_2") (pintype "passive"))
    )
    (net (code "54") (name "Net-(J4-Pad2)") (class "Default")
      (node (ref "J4") (pin "2") (pinfunction "2_2") (pintype "passive"))
      (node (ref "R10") (pin "2") (pinfunction "2_2") (pintype "passive"))
    )
    (net (code "55") (name "Net-(J4-Pad4)") (class "Default")
      (node (ref "J4") (pin "4") (pinfunction "4_4") (pintype "passive"))
      (node (ref "R13") (pin "2") (pinfunction "2_2") (pintype "passive"))
    )
    (net (code "56") (name "Net-(J4-Pad5)") (class "Default")
      (node (ref "J4") (pin "5") (pinfunction "5_5") (pintype "passive"))
      (node (ref "R15") (pin "2") (pinfunction "2_2") (pintype "passive"))
    )
    (net (code "57") (name "Net-(J4-Pad7)") (class "Default")
      (node (ref "J4") (pin "7") (pinfunction "7_7") (pintype "passive"))
      (node (ref "R22") (pin "2") (pinfunction "2_2") (pintype "passive"))
    )
    (net (code "58") (name "Net-(J4-Pad8)") (class "Default")
      (node (ref "J4") (pin "8") (pinfunction "8_8") (pintype "passive"))
      (node (ref "R24") (pin "2") (pinfunction "2_2") (pintype "passive"))
    )
    (net (code "59") (name "Net-(J4-Pad10)") (class "Default")
      (node (ref "J4") (pin "10") (pinfunction "10_10") (pintype "passive"))
      (node (ref "R26") (pin "2") (pinfunction "2_2") (pintype "passive"))
    )
    (net (code "60") (name "Net-(J4-Pad11)") (class "Default")
      (node (ref "J4") (pin "11") (pinfunction "11_11") (pintype "passive"))
      (node (ref "R28") (pin "2") (pinfunction "2_2") (pintype "passive"))
    )
    (net (code "61") (name "Net-(LED1-A)") (class "Default")
      (node (ref "LED1") (pin "1") (pinfunction "A_1") (pintype "passive"))
      (node (ref "R29") (pin "2") (pinfunction "2_2") (pintype "passive"))
    )
    (net (code "62") (name "Net-(LED2-A)") (class "Default")
      (node (ref "LED2") (pin "1") (pinfunction "A_1") (pintype "passive"))
      (node (ref "R17") (pin "2") (pinfunction "2_2") (pintype "passive"))
    )
    (net (code "63") (name "Net-(LED3-A)") (class "Default")
      (node (ref "LED3") (pin "1") (pinfunction "A_1") (pintype "passive"))
      (node (ref "R20") (pin "2") (pinfunction "2_2") (pintype "passive"))
    )
    (net (code "64") (name "Net-(LED4-A)") (class "Default")
      (node (ref "LED4") (pin "1") (pinfunction "A_1") (pintype "passive"))
      (node (ref "R19") (pin "2") (pinfunction "2_2") (pintype "passive"))
    )
    (net (code "65") (name "Net-(U1-BOOT0)") (class "Default")
      (node (ref "R1") (pin "2") (pinfunction "2_2") (pintype "passive"))
      (node (ref "U1") (pin "44") (pinfunction "BOOT0_44") (pintype "input"))
    )
    (net (code "66") (name "Net-(U4-BOOT)") (class "Default")
      (node (ref "C7") (pin "1") (pinfunction "1_1") (pintype "passive"))
      (node (ref "U4") (pin "1") (pinfunction "BOOT_1") (pintype "output"))
    )
    (net (code "67") (name "Net-(U4-VSENSE)") (class "Default")
      (node (ref "R18") (pin "1") (pinfunction "1_1") (pintype "passive"))
      (node (ref "R21") (pin "2") (pinfunction "2_2") (pintype "passive"))
      (node (ref "U4") (pin "4") (pinfunction "VSENSE_4") (pintype "input"))
    )
    (net (code "68") (name "unconnected-(J1-Pad6)") (class "Default")
      (node (ref "J1") (pin "6") (pinfunction "6_6") (pintype "passive"))
    )
    (net (code "69") (name "unconnected-(J1-Pad7)") (class "Default")
      (node (ref "J1") (pin "7") (pinfunction "7_7") (pintype "passive"))
    )
    (net (code "70") (name "unconnected-(J1-Pad8)") (class "Default")
      (node (ref "J1") (pin "8") (pinfunction "8_8") (pintype "passive"))
    )
    (net (code "71") (name "unconnected-(U1-PA2-Pad12)") (class "Default")
      (node (ref "U1") (pin "12") (pinfunction "PA2_12") (pintype "bidirectional"))
    )
    (net (code "72") (name "unconnected-(U1-PB6-Pad42)") (class "Default")
      (node (ref "U1") (pin "42") (pinfunction "PB6_42") (pintype "bidirectional"))
    )
    (net (code "73") (name "unconnected-(U1-PB7-Pad43)") (class "Default")
      (node (ref "U1") (pin "43") (pinfunction "PB7_43") (pintype "bidirectional"))
    )
    (net (code "74") (name "unconnected-(U1-PB8-Pad45)") (class "Default")
      (node (ref "U1") (pin "45") (pinfunction "PB8_45") (pintype "bidirectional"))
    )
    (net (code "75") (name "unconnected-(U1-PB9-Pad46)") (class "Default")
      (node (ref "U1") (pin "46") (pinfunction "PB9_46") (pintype "bidirectional"))
    )
    (net (code "76") (name "unconnected-(U1-PC13-Pad2)") (class "Default")
      (node (ref "U1") (pin "2") (pinfunction "PC13_2") (pintype "bidirectional"))
    )
    (net (code "77") (name "unconnected-(U1-PC14-OSC32_IN-Pad3)") (class "Default")
      (node (ref "U1") (pin "3") (pinfunction "PC14-OSC32_IN_3") (pintype "bidirectional"))
    )
    (net (code "78") (name "unconnected-(U1-PC15-OSC32_OUT-Pad4)") (class "Default")
      (node (ref "U1") (pin "4") (pinfunction "PC15-OSC32_OUT_4") (pintype "bidirectional"))
    )
    (net (code "79") (name "unconnected-(U1-PF6-Pad35)") (class "Default")
      (node (ref "U1") (pin "35") (pinfunction "PF6_35") (pintype "bidirectional"))
    )
    (net (code "80") (name "unconnected-(U1-PF7-Pad36)") (class "Default")
      (node (ref "U1") (pin "36") (pinfunction "PF7_36") (pintype "bidirectional"))
    )
    (net (code "81") (name "unconnected-(U4-ENA-Pad5)") (class "Default")
      (node (ref "U4") (pin "5") (pinfunction "ENA_5") (pintype "input+no_connect"))
    )
    (net (code "82") (name "unconnected-(U4-NC-Pad2)") (class "Default")
      (node (ref "U4") (pin "2") (pinfunction "NC_2") (pintype "passive+no_connect"))
    )
    (net (code "83") (name "unconnected-(U4-NC-Pad3)") (class "Default")
      (node (ref "U4") (pin "3") (pinfunction "NC_3") (pintype "passive+no_connect"))
    )
  )
)
